# RocketPDBV4.net
KiCad netlist of a schematic drawn in EasyEDA
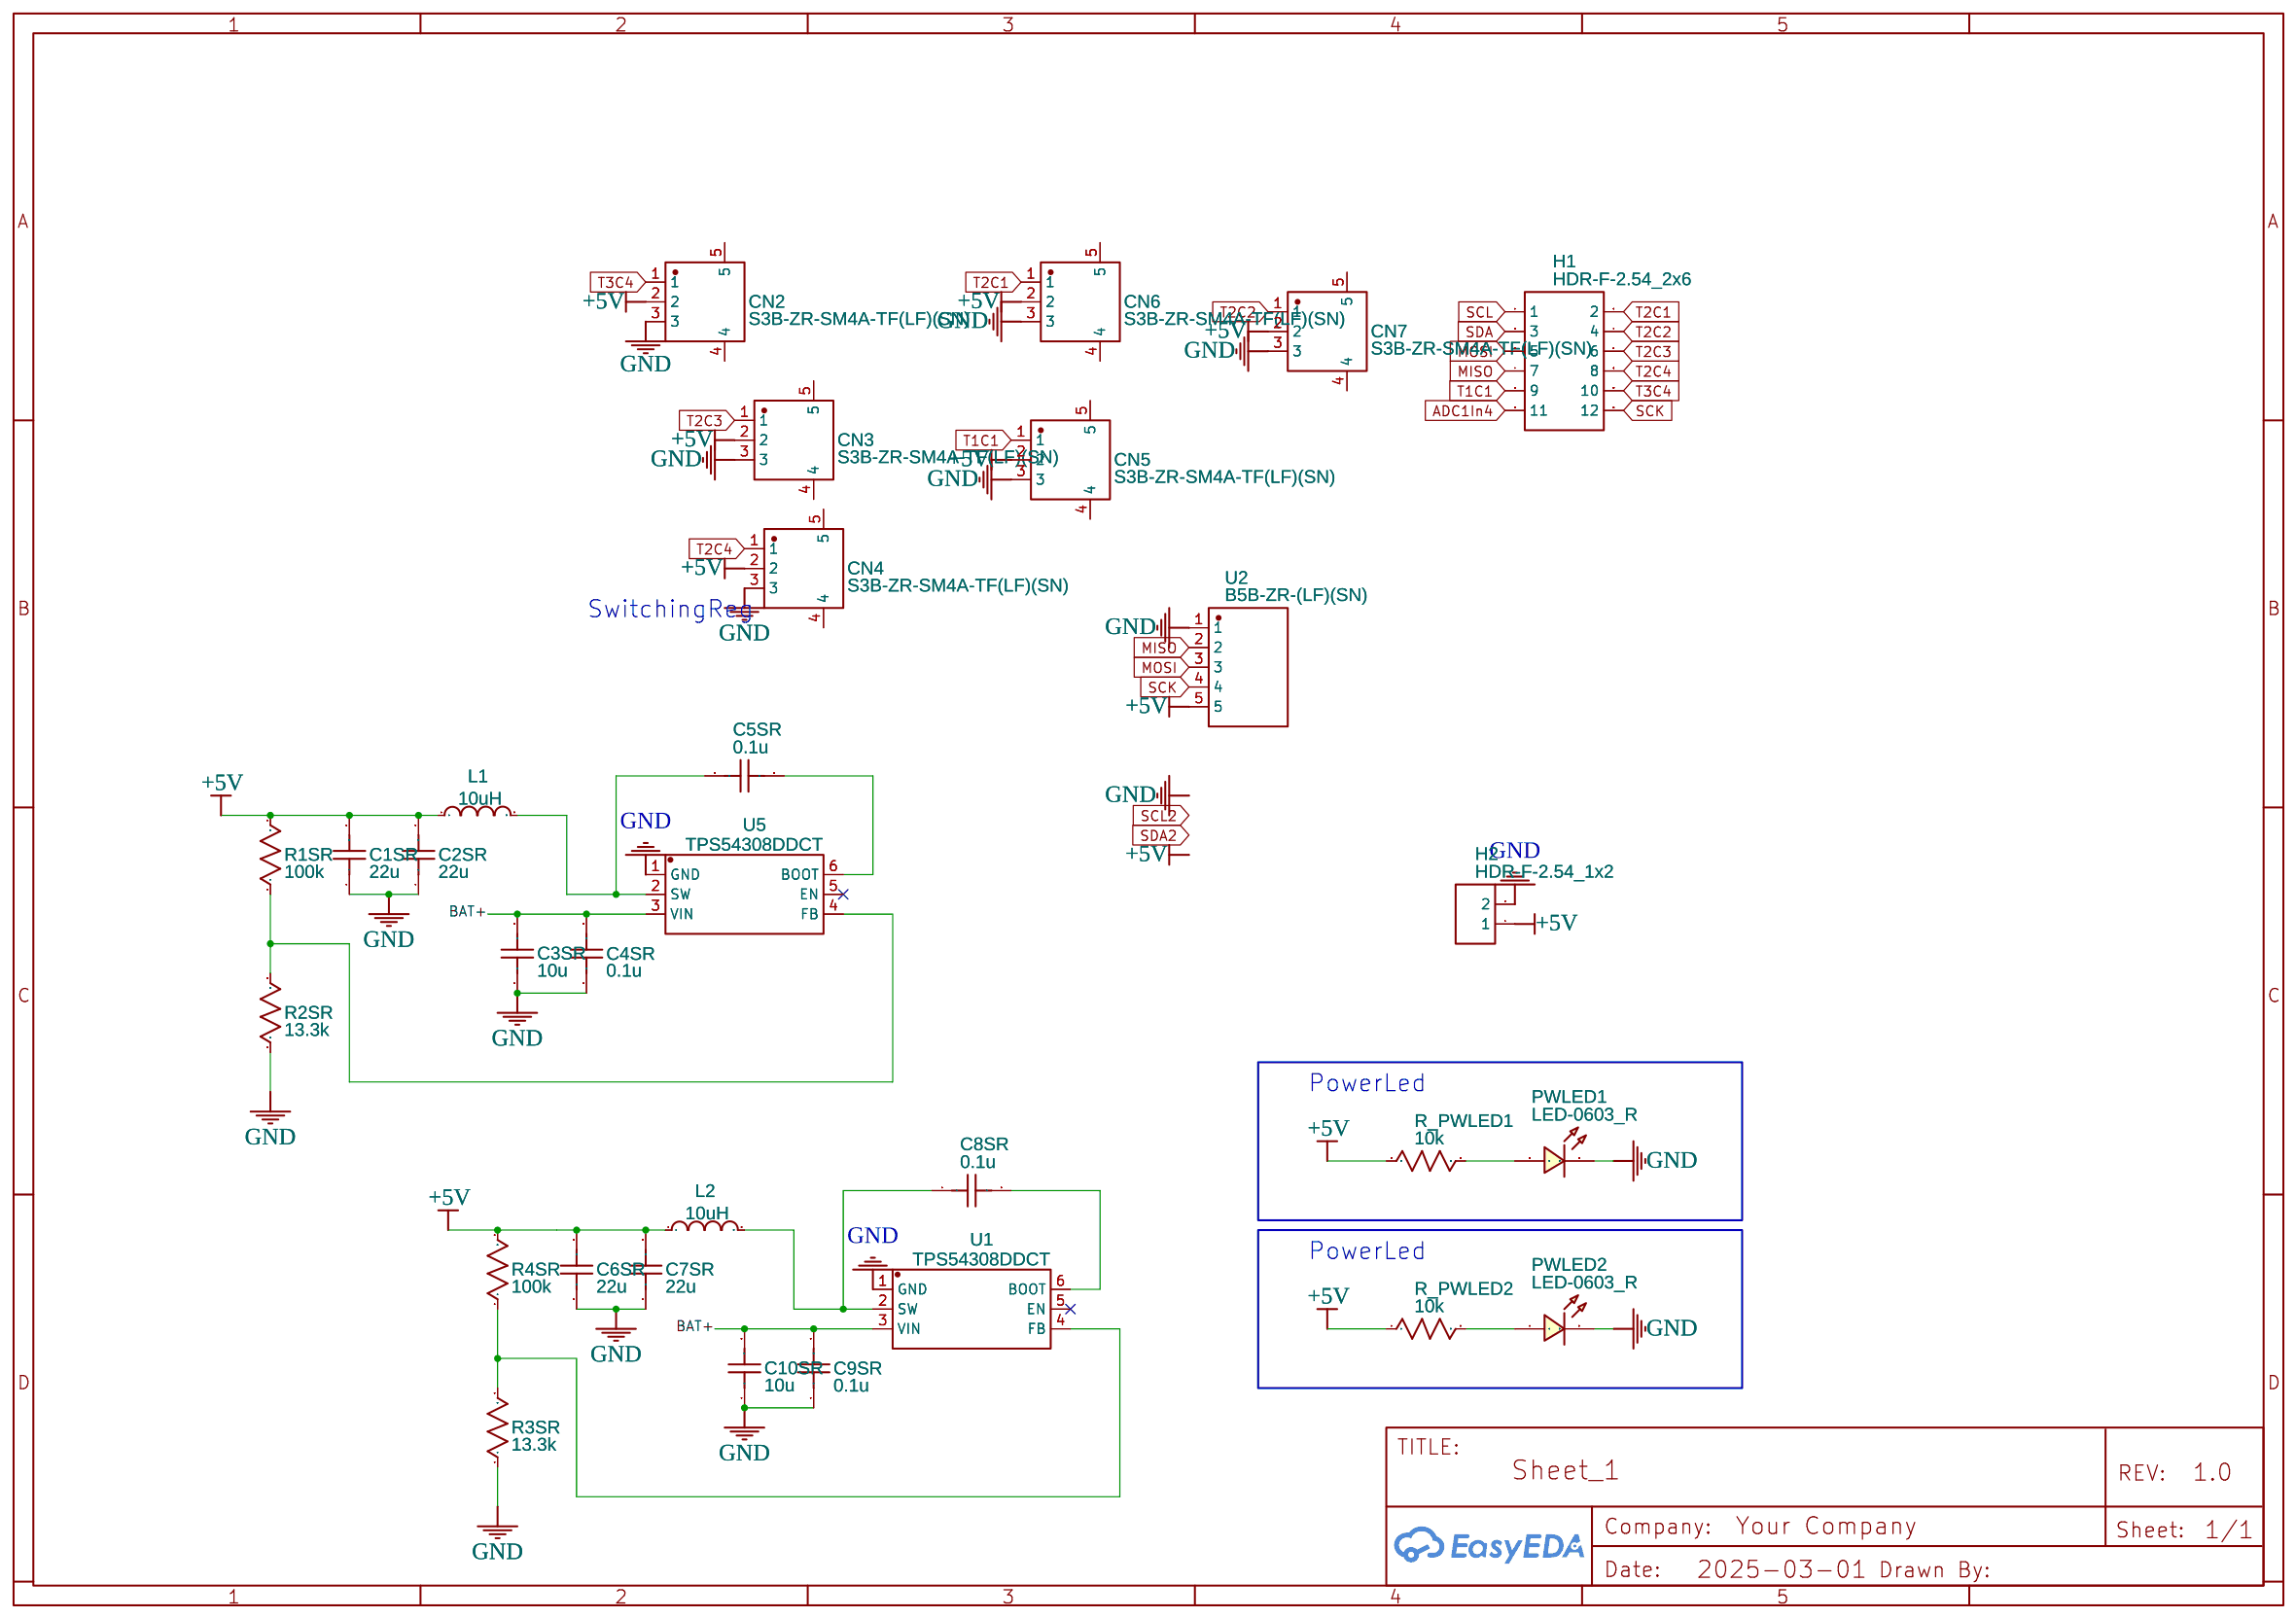
[diagram p0: schematic sheet]

(export (version "E")
  (design (tool "Eeschema 10.0.6"))
  (components
    (comp (ref "C1SR") (value "22u") (libsource (lib "") (part "C_0603_US_1")))
    (comp (ref "C2SR") (value "22u") (libsource (lib "") (part "C_0603_US_5")))
    (comp (ref "C3SR") (value "10u") (libsource (lib "") (part "C_0603_US_8")))
    (comp (ref "C4SR") (value "0.1u") (libsource (lib "") (part "C_0603_US_9")))
    (comp (ref "C5SR") (value "0.1u") (libsource (lib "") (part "C_0603_US_6")))
    (comp (ref "C6SR") (value "22u") (libsource (lib "") (part "C_0603_US")))
    (comp (ref "C7SR") (value "22u") (libsource (lib "") (part "C_0603_US_4")))
    (comp (ref "C8SR") (value "0.1u") (libsource (lib "") (part "C_0603_US_3")))
    (comp (ref "C9SR") (value "0.1u") (libsource (lib "") (part "C_0603_US_7")))
    (comp (ref "C10SR") (value "10u") (libsource (lib "") (part "C_0603_US_2")))
    (comp (ref "CN2")
      (value "S3B-ZR-SM4A-TF(LF)(SN)")
      (fields (field (name "Manufacturer") "JST"))
      (libsource (lib "") (part "S3B-ZR-SM4A-TF(LF)(SN)"))
    )
    (comp (ref "CN3")
      (value "S3B-ZR-SM4A-TF(LF)(SN)")
      (fields (field (name "Manufacturer") "JST"))
      (libsource (lib "") (part "S3B-ZR-SM4A-TF(LF)(SN)"))
    )
    (comp (ref "CN4")
      (value "S3B-ZR-SM4A-TF(LF)(SN)")
      (fields (field (name "Manufacturer") "JST"))
      (libsource (lib "") (part "S3B-ZR-SM4A-TF(LF)(SN)"))
    )
    (comp (ref "CN5")
      (value "S3B-ZR-SM4A-TF(LF)(SN)")
      (fields (field (name "Manufacturer") "JST"))
      (libsource (lib "") (part "S3B-ZR-SM4A-TF(LF)(SN)"))
    )
    (comp (ref "CN6")
      (value "S3B-ZR-SM4A-TF(LF)(SN)")
      (fields (field (name "Manufacturer") "JST"))
      (libsource (lib "") (part "S3B-ZR-SM4A-TF(LF)(SN)"))
    )
    (comp (ref "CN7")
      (value "S3B-ZR-SM4A-TF(LF)(SN)")
      (fields (field (name "Manufacturer") "JST"))
      (libsource (lib "") (part "S3B-ZR-SM4A-TF(LF)(SN)"))
    )
    (comp (ref "H1") (value "HDR-F-2.54_2x6") (libsource (lib "") (part "HDR-F-2.54_2x6")))
    (comp (ref "H2") (value "HDR-F-2.54_1x2") (libsource (lib "") (part "HDR-F-2.54_1x2")))
    (comp (ref "L1") (value "10uH") (libsource (lib "") (part "L0603_US")))
    (comp (ref "L2") (value "10uH") (libsource (lib "") (part "L0603_US_1")))
    (comp (ref "PWLED1")
      (value "LED-0603_R")
      (fields
        (field (name "Manufacturer Part") "19-217/R6C-AL1M2VY/3T")
        (field (name "Manufacturer") "EVERLIGHT(台湾亿光)")
      )
      (libsource (lib "") (part "LED-0603_R"))
    )
    (comp (ref "PWLED2")
      (value "LED-0603_R")
      (fields
        (field (name "Manufacturer Part") "19-217/R6C-AL1M2VY/3T")
        (field (name "Manufacturer") "EVERLIGHT(台湾亿光)")
      )
      (libsource (lib "") (part "LED-0603_R"))
    )
    (comp (ref "R1SR") (value "100k") (libsource (lib "") (part "R_0603_US")))
    (comp (ref "R2SR") (value "13.3k") (libsource (lib "") (part "R_0603_US_3")))
    (comp (ref "R3SR") (value "13.3k") (libsource (lib "") (part "R_0603_US_2")))
    (comp (ref "R4SR") (value "100k") (libsource (lib "") (part "R_0603_US_4")))
    (comp (ref "R_PWLED1") (value "10k") (libsource (lib "") (part "R_0603_US_1")))
    (comp (ref "R_PWLED2") (value "10k") (libsource (lib "") (part "R_0603_US_1")))
    (comp (ref "U1")
      (value "TPS54308DDCT")
      (fields (field (name "Manufacturer") "TI(德州仪器)"))
      (libsource (lib "") (part "TPS54308DDCT"))
    )
    (comp (ref "U2")
      (value "B5B-ZR-(LF)(SN)")
      (fields (field (name "Manufacturer Part") "B5B-ZR(LF)(SN)") (field (name "Manufacturer") "JST"))
      (libsource (lib "") (part "B5B-ZR-(LF)(SN)"))
    )
    (comp (ref "U5")
      (value "TPS54308DDCT")
      (fields (field (name "Manufacturer") "TI(德州仪器)"))
      (libsource (lib "") (part "TPS54308DDCT"))
    )
  )
  (nets
    (net (code "1") (name "+5V") (class "Default")
      (node (ref "C1SR") (pin "2") (pinfunction "2_2") (pintype "unspecified"))
      (node (ref "C2SR") (pin "2") (pinfunction "2_2") (pintype "unspecified"))
      (node (ref "C6SR") (pin "2") (pinfunction "2_2") (pintype "unspecified"))
      (node (ref "C7SR") (pin "2") (pinfunction "2_2") (pintype "unspecified"))
      (node (ref "CN2") (pin "2") (pinfunction "2_2") (pintype "unspecified"))
      (node (ref "CN3") (pin "2") (pinfunction "2_2") (pintype "unspecified"))
      (node (ref "CN4") (pin "2") (pinfunction "2_2") (pintype "unspecified"))
      (node (ref "CN5") (pin "2") (pinfunction "2_2") (pintype "unspecified"))
      (node (ref "CN6") (pin "2") (pinfunction "2_2") (pintype "unspecified"))
      (node (ref "CN7") (pin "2") (pinfunction "2_2") (pintype "unspecified"))
      (node (ref "H2") (pin "1") (pinfunction "1_1") (pintype "input"))
      (node (ref "L1") (pin "1") (pinfunction "1_1") (pintype "unspecified"))
      (node (ref "L2") (pin "1") (pinfunction "1_1") (pintype "unspecified"))
      (node (ref "R1SR") (pin "2") (pinfunction "2_2") (pintype "unspecified"))
      (node (ref "R4SR") (pin "2") (pinfunction "2_2") (pintype "unspecified"))
      (node (ref "R_PWLED1") (pin "1") (pinfunction "1_1") (pintype "unspecified"))
      (node (ref "R_PWLED2") (pin "1") (pinfunction "1_1") (pintype "unspecified"))
      (node (ref "U2") (pin "5") (pinfunction "5_5") (pintype "unspecified"))
    )
    (net (code "2") (name "/BAT+") (class "Default")
      (node (ref "C10SR") (pin "2") (pinfunction "2_2") (pintype "unspecified"))
      (node (ref "C3SR") (pin "2") (pinfunction "2_2") (pintype "unspecified"))
      (node (ref "C4SR") (pin "2") (pinfunction "2_2") (pintype "unspecified"))
      (node (ref "C9SR") (pin "2") (pinfunction "2_2") (pintype "unspecified"))
      (node (ref "U1") (pin "3") (pinfunction "VIN_3") (pintype "unspecified"))
      (node (ref "U5") (pin "3") (pinfunction "VIN_3") (pintype "unspecified"))
    )
    (net (code "3") (name "ADC1In4") (class "Default")
      (node (ref "H1") (pin "11") (pinfunction "11_11") (pintype "input"))
    )
    (net (code "4") (name "GND") (class "Default")
      (node (ref "C10SR") (pin "1") (pinfunction "1_1") (pintype "unspecified"))
      (node (ref "C1SR") (pin "1") (pinfunction "1_1") (pintype "unspecified"))
      (node (ref "C2SR") (pin "1") (pinfunction "1_1") (pintype "unspecified"))
      (node (ref "C3SR") (pin "1") (pinfunction "1_1") (pintype "unspecified"))
      (node (ref "C4SR") (pin "1") (pinfunction "1_1") (pintype "unspecified"))
      (node (ref "C6SR") (pin "1") (pinfunction "1_1") (pintype "unspecified"))
      (node (ref "C7SR") (pin "1") (pinfunction "1_1") (pintype "unspecified"))
      (node (ref "C9SR") (pin "1") (pinfunction "1_1") (pintype "unspecified"))
      (node (ref "CN2") (pin "3") (pinfunction "3_3") (pintype "unspecified"))
      (node (ref "CN3") (pin "3") (pinfunction "3_3") (pintype "unspecified"))
      (node (ref "CN4") (pin "3") (pinfunction "3_3") (pintype "unspecified"))
      (node (ref "CN5") (pin "3") (pinfunction "3_3") (pintype "unspecified"))
      (node (ref "CN6") (pin "3") (pinfunction "3_3") (pintype "unspecified"))
      (node (ref "CN7") (pin "3") (pinfunction "3_3") (pintype "unspecified"))
      (node (ref "H2") (pin "2") (pinfunction "2_2") (pintype "input"))
      (node (ref "PWLED1") (pin "2") (pinfunction "2_2") (pintype "unspecified"))
      (node (ref "PWLED2") (pin "2") (pinfunction "2_2") (pintype "unspecified"))
      (node (ref "R2SR") (pin "1") (pinfunction "1_1") (pintype "unspecified"))
      (node (ref "R3SR") (pin "1") (pinfunction "1_1") (pintype "unspecified"))
      (node (ref "U1") (pin "1") (pinfunction "GND_1") (pintype "unspecified"))
      (node (ref "U2") (pin "1") (pinfunction "1_1") (pintype "unspecified"))
      (node (ref "U5") (pin "1") (pinfunction "GND_1") (pintype "unspecified"))
    )
    (net (code "5") (name "MISO") (class "Default")
      (node (ref "H1") (pin "7") (pinfunction "7_7") (pintype "input"))
      (node (ref "U2") (pin "2") (pinfunction "2_2") (pintype "unspecified"))
    )
    (net (code "6") (name "MOSI") (class "Default")
      (node (ref "H1") (pin "5") (pinfunction "5_5") (pintype "input"))
      (node (ref "U2") (pin "3") (pinfunction "3_3") (pintype "unspecified"))
    )
    (net (code "7") (name "Net-(PWLED1-Pad1)") (class "Default")
      (node (ref "PWLED1") (pin "1") (pinfunction "1_1") (pintype "unspecified"))
      (node (ref "R_PWLED1") (pin "2") (pinfunction "2_2") (pintype "unspecified"))
    )
    (net (code "8") (name "Net-(PWLED2-Pad1)") (class "Default")
      (node (ref "PWLED2") (pin "1") (pinfunction "1_1") (pintype "unspecified"))
      (node (ref "R_PWLED2") (pin "2") (pinfunction "2_2") (pintype "unspecified"))
    )
    (net (code "9") (name "Net-(U1-BOOT)") (class "Default")
      (node (ref "C8SR") (pin "2") (pinfunction "2_2") (pintype "unspecified"))
      (node (ref "U1") (pin "6") (pinfunction "BOOT_6") (pintype "unspecified"))
    )
    (net (code "10") (name "Net-(U1-FB)") (class "Default")
      (node (ref "R3SR") (pin "2") (pinfunction "2_2") (pintype "unspecified"))
      (node (ref "R4SR") (pin "1") (pinfunction "1_1") (pintype "unspecified"))
      (node (ref "U1") (pin "4") (pinfunction "FB_4") (pintype "unspecified"))
    )
    (net (code "11") (name "Net-(U1-SW)") (class "Default")
      (node (ref "C8SR") (pin "1") (pinfunction "1_1") (pintype "unspecified"))
      (node (ref "L2") (pin "2") (pinfunction "2_2") (pintype "unspecified"))
      (node (ref "U1") (pin "2") (pinfunction "SW_2") (pintype "unspecified"))
    )
    (net (code "12") (name "Net-(U5-BOOT)") (class "Default")
      (node (ref "C5SR") (pin "2") (pinfunction "2_2") (pintype "unspecified"))
      (node (ref "U5") (pin "6") (pinfunction "BOOT_6") (pintype "unspecified"))
    )
    (net (code "13") (name "Net-(U5-FB)") (class "Default")
      (node (ref "R1SR") (pin "1") (pinfunction "1_1") (pintype "unspecified"))
      (node (ref "R2SR") (pin "2") (pinfunction "2_2") (pintype "unspecified"))
      (node (ref "U5") (pin "4") (pinfunction "FB_4") (pintype "unspecified"))
    )
    (net (code "14") (name "Net-(U5-SW)") (class "Default")
      (node (ref "C5SR") (pin "1") (pinfunction "1_1") (pintype "unspecified"))
      (node (ref "L1") (pin "2") (pinfunction "2_2") (pintype "unspecified"))
      (node (ref "U5") (pin "2") (pinfunction "SW_2") (pintype "unspecified"))
    )
    (net (code "15") (name "SCK") (class "Default")
      (node (ref "H1") (pin "12") (pinfunction "12_12") (pintype "input"))
      (node (ref "U2") (pin "4") (pinfunction "4_4") (pintype "unspecified"))
    )
    (net (code "16") (name "SCL") (class "Default")
      (node (ref "H1") (pin "1") (pinfunction "1_1") (pintype "input"))
    )
    (net (code "18") (name "SDA") (class "Default")
      (node (ref "H1") (pin "3") (pinfunction "3_3") (pintype "input"))
    )
    (net (code "20") (name "T1C1") (class "Default")
      (node (ref "CN5") (pin "1") (pinfunction "1_1") (pintype "unspecified"))
      (node (ref "H1") (pin "9") (pinfunction "9_9") (pintype "input"))
    )
    (net (code "21") (name "T2C1") (class "Default")
      (node (ref "CN6") (pin "1") (pinfunction "1_1") (pintype "unspecified"))
      (node (ref "H1") (pin "2") (pinfunction "2_2") (pintype "input"))
    )
    (net (code "22") (name "T2C2") (class "Default")
      (node (ref "CN7") (pin "1") (pinfunction "1_1") (pintype "unspecified"))
      (node (ref "H1") (pin "4") (pinfunction "4_4") (pintype "input"))
    )
    (net (code "23") (name "T2C3") (class "Default")
      (node (ref "CN3") (pin "1") (pinfunction "1_1") (pintype "unspecified"))
      (node (ref "H1") (pin "6") (pinfunction "6_6") (pintype "input"))
    )
    (net (code "24") (name "T2C4") (class "Default")
      (node (ref "CN4") (pin "1") (pinfunction "1_1") (pintype "unspecified"))
      (node (ref "H1") (pin "8") (pinfunction "8_8") (pintype "input"))
    )
    (net (code "25") (name "T3C4") (class "Default")
      (node (ref "CN2") (pin "1") (pinfunction "1_1") (pintype "unspecified"))
      (node (ref "H1") (pin "10") (pinfunction "10_10") (pintype "input"))
    )
    (net (code "26") (name "unconnected-(CN2-Pad4)") (class "Default")
      (node (ref "CN2") (pin "4") (pinfunction "4_4") (pintype "unspecified"))
    )
    (net (code "27") (name "unconnected-(CN2-Pad5)") (class "Default")
      (node (ref "CN2") (pin "5") (pinfunction "5_5") (pintype "unspecified"))
    )
    (net (code "28") (name "unconnected-(CN3-Pad4)") (class "Default")
      (node (ref "CN3") (pin "4") (pinfunction "4_4") (pintype "unspecified"))
    )
    (net (code "29") (name "unconnected-(CN3-Pad5)") (class "Default")
      (node (ref "CN3") (pin "5") (pinfunction "5_5") (pintype "unspecified"))
    )
    (net (code "30") (name "unconnected-(CN4-Pad4)") (class "Default")
      (node (ref "CN4") (pin "4") (pinfunction "4_4") (pintype "unspecified"))
    )
    (net (code "31") (name "unconnected-(CN4-Pad5)") (class "Default")
      (node (ref "CN4") (pin "5") (pinfunction "5_5") (pintype "unspecified"))
    )
    (net (code "32") (name "unconnected-(CN5-Pad4)") (class "Default")
      (node (ref "CN5") (pin "4") (pinfunction "4_4") (pintype "unspecified"))
    )
    (net (code "33") (name "unconnected-(CN5-Pad5)") (class "Default")
      (node (ref "CN5") (pin "5") (pinfunction "5_5") (pintype "unspecified"))
    )
    (net (code "34") (name "unconnected-(CN6-Pad4)") (class "Default")
      (node (ref "CN6") (pin "4") (pinfunction "4_4") (pintype "unspecified"))
    )
    (net (code "35") (name "unconnected-(CN6-Pad5)") (class "Default")
      (node (ref "CN6") (pin "5") (pinfunction "5_5") (pintype "unspecified"))
    )
    (net (code "36") (name "unconnected-(CN7-Pad4)") (class "Default")
      (node (ref "CN7") (pin "4") (pinfunction "4_4") (pintype "unspecified"))
    )
    (net (code "37") (name "unconnected-(CN7-Pad5)") (class "Default")
      (node (ref "CN7") (pin "5") (pinfunction "5_5") (pintype "unspecified"))
    )
    (net (code "38") (name "unconnected-(U1-EN-Pad5)") (class "Default")
      (node (ref "U1") (pin "5") (pinfunction "EN_5") (pintype "unspecified+no_connect"))
    )
    (net (code "39") (name "unconnected-(U5-EN-Pad5)") (class "Default")
      (node (ref "U5") (pin "5") (pinfunction "EN_5") (pintype "unspecified+no_connect"))
    )
  )
)
